# 2__ARM.net
KiCad netlist of a schematic drawn in Altium Designer
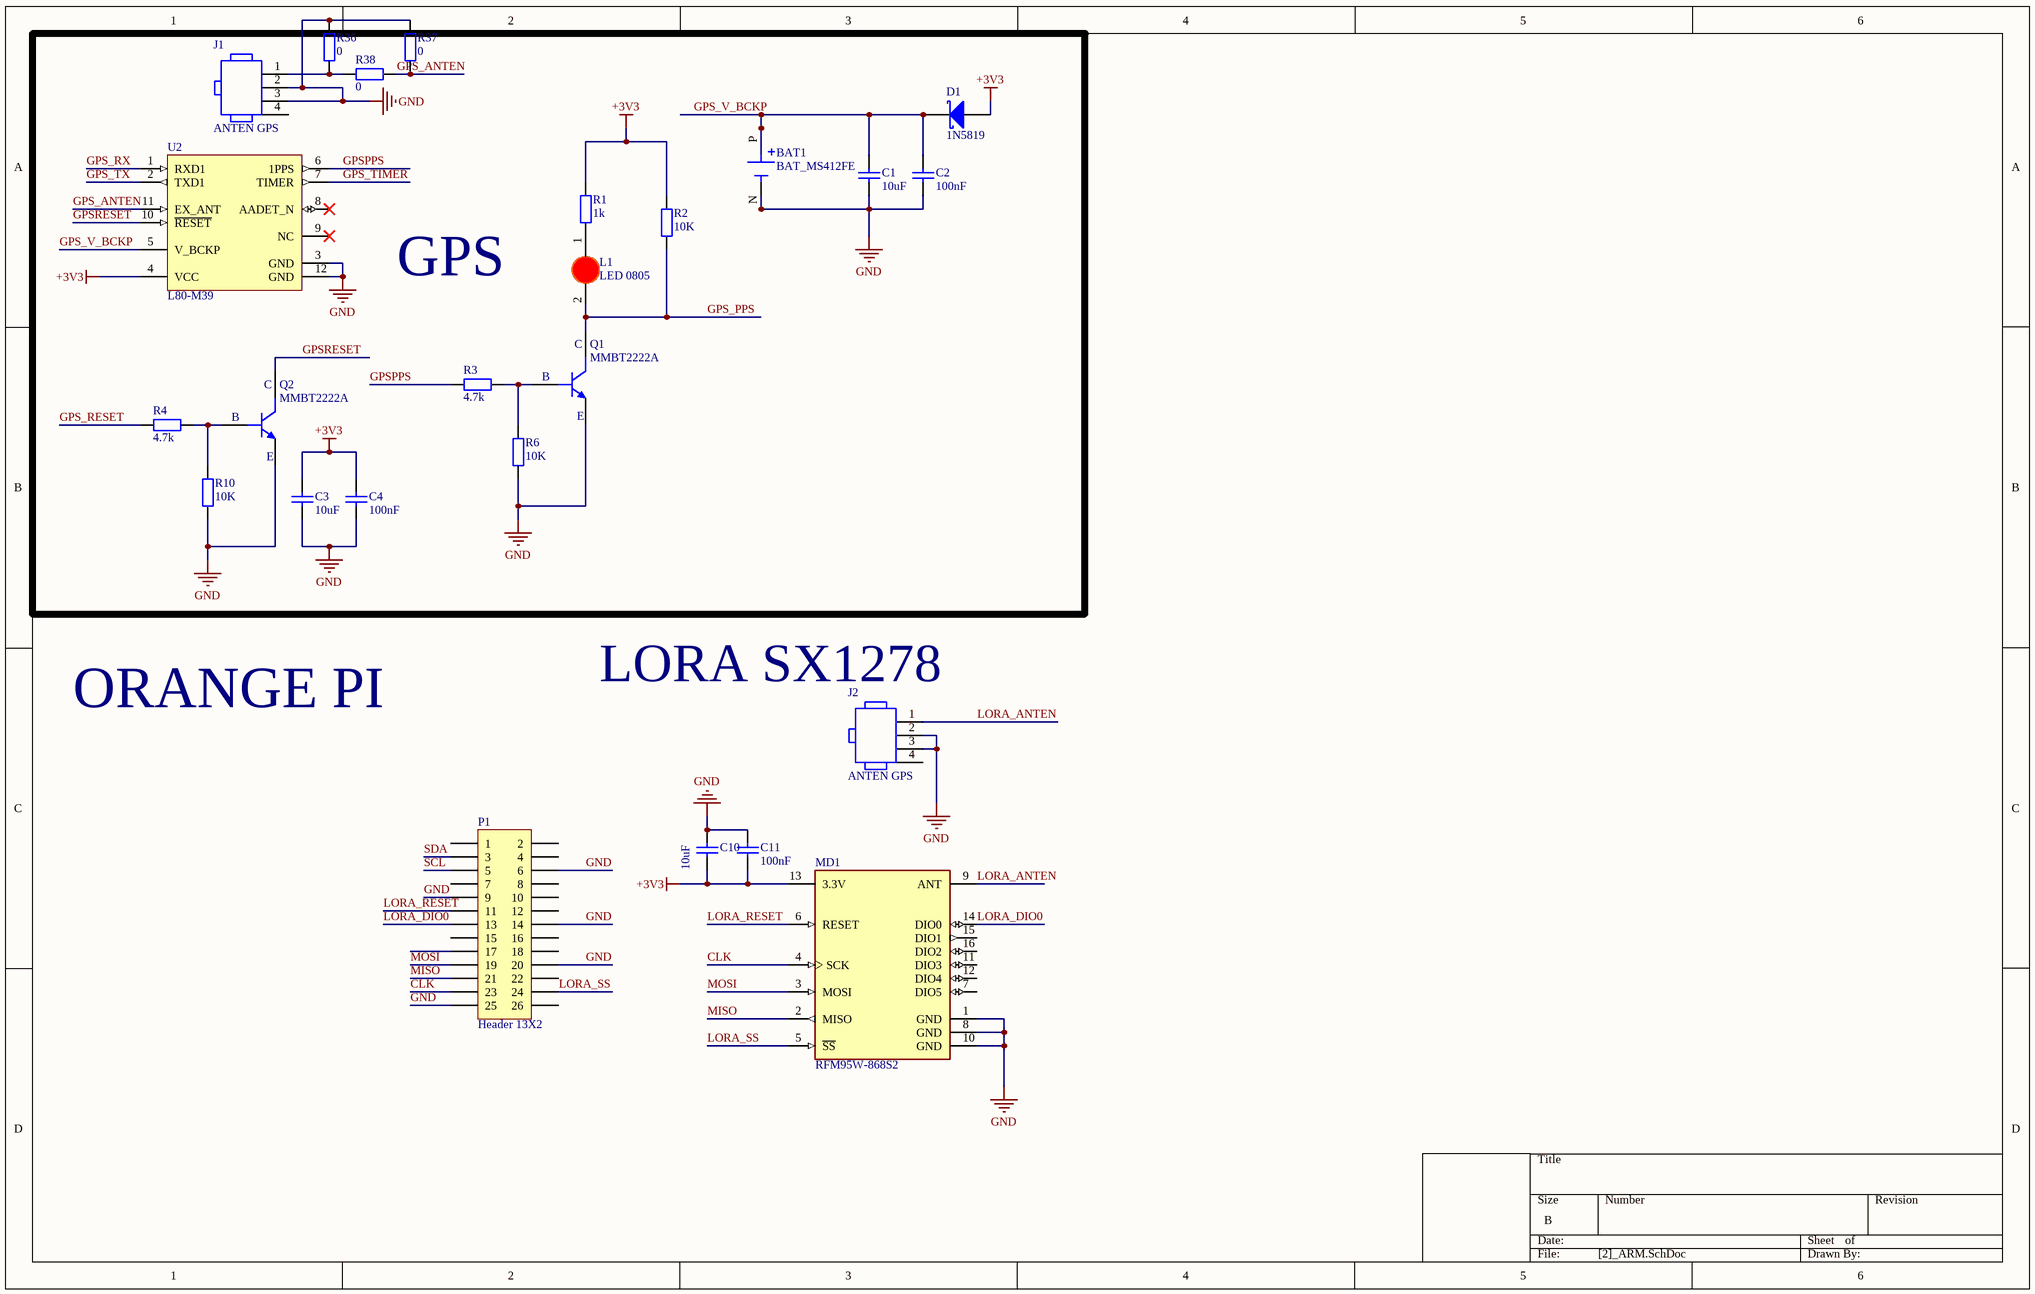
[diagram p0: [2]_ARM.SchDoc]

(export (version "E")
  (design (tool "Eeschema 10.0.6"))
  (components
    (comp (ref "BAT1")
      (value "BAT_MS412FE")
      (footprint "MS412FE")
      (libsource (lib "COMPONENT_INS") (part "BAT_MS412FE"))
    )
    (comp (ref "C1")
      (value "10uF")
      (footprint "tu 0603")
      (description "Dán")
      (libsource (lib "Altium_Lib_by_KhueNguyenCreator") (part "Tu 0603 105 16V 20%"))
    )
    (comp (ref "C2")
      (value "100nF")
      (footprint "tu 0603")
      (description "Dán")
      (libsource (lib "Altium_Lib_by_KhueNguyenCreator") (part "Tu 0603 104 50V 10%"))
    )
    (comp (ref "C3")
      (value "10uF")
      (footprint "tu 0603")
      (description "Dán")
      (libsource (lib "Altium_Lib_by_KhueNguyenCreator") (part "Tu 0603 105 16V 20%"))
    )
    (comp (ref "C4")
      (value "100nF")
      (footprint "tu 0603")
      (description "Dán")
      (libsource (lib "Altium_Lib_by_KhueNguyenCreator") (part "Tu 0603 104 50V 10%"))
    )
    (comp (ref "C10")
      (value "10uF")
      (footprint "tu 0603")
      (description "Dán")
      (libsource (lib "Altium_Lib_by_KhueNguyenCreator") (part "Tu 0603 105 16V 20%"))
    )
    (comp (ref "C11")
      (value "100nF")
      (footprint "tu 0603")
      (description "Dán")
      (libsource (lib "Altium_Lib_by_KhueNguyenCreator") (part "Tu 0603 104 50V 10%"))
    )
    (comp (ref "D1")
      (value "1N5819")
      (footprint "DO-214AA")
      (description "DIODE SCHOTTKY 1A 40V SMA DO-214AA")
      (fields (field (name "MANUFACTURER") "Fairchild") (field (name "PART NUMBER") "SS14"))
      (libsource (lib "COMPONENT_INS") (part "DIO_SS14"))
    )
    (comp (ref "J1")
      (value "ANTEN GPS")
      (footprint "TG-RECE-20369-001E-4_V")
      (description "RF Connector, Onboard Receptacle, IPEX MHFIII")
      (fields (field (name "MANUFACTURER") "Taoglas") (field (name "PARTNUMBER") "RECE-20369-001E-01"))
      (libsource (lib "Altium Content Vault") (part "TG-RECE-20369-001E-01-4"))
    )
    (comp (ref "J2")
      (value "ANTEN GPS")
      (footprint "TG-RECE-20369-001E-4_V")
      (description "RF Connector, Onboard Receptacle, IPEX MHFIII")
      (fields (field (name "MANUFACTURER") "Taoglas") (field (name "PARTNUMBER") "RECE-20369-001E-01"))
      (libsource (lib "Altium Content Vault") (part "TG-RECE-20369-001E-01-4"))
    )
    (comp (ref "L1")
      (value "LED 0805")
      (footprint "LED-0805-Red")
      (description "Dán")
      (libsource (lib "Altium_Lib_by_KhueNguyenCreator") (part "LED 0805 Do"))
    )
    (comp (ref "MD1")
      (value "RFM95W-868S2")
      (footprint "FP-RFM95W-868S2-MFG")
      (description "RX TXRX MODULE ISM < 1GHZ SMD")
      (libsource (lib "Altium Content Vault") (part "17626aa6fba47fab2b206b7c140802e"))
    )
    (comp (ref "P1")
      (value "Header 13X2")
      (footprint "HDR2X13")
      (description "Header, 13-Pin, Dual row")
      (fields (field (name "PUBLISHER") "Altium Limited"))
      (libsource (lib "Miscellaneous Connectors") (part "Header 13X2"))
    )
    (comp (ref "Q1")
      (value "MMBT2222A")
      (footprint "SOT_23_3")
      (description "MMBT2222A NPN 40V 0.6A")
      (fields (field (name "MANUFACTURER") "OEM"))
      (libsource (lib "COMPONENT_INS") (part "BJT_NPN_MMBT2222A"))
    )
    (comp (ref "Q2")
      (value "MMBT2222A")
      (footprint "SOT_23_3")
      (description "MMBT2222A NPN 40V 0.6A")
      (fields (field (name "MANUFACTURER") "OEM"))
      (libsource (lib "COMPONENT_INS") (part "BJT_NPN_MMBT2222A"))
    )
    (comp (ref "R1")
      (value "1k")
      (footprint "tro smd 0603")
      (description "Dán")
      (libsource (lib "Altium_Lib_by_KhueNguyenCreator") (part "Tro 0603 1% 4.3 k"))
    )
    (comp (ref "R2")
      (value "10K")
      (footprint "tro smd 0603")
      (description "Dán")
      (libsource (lib "Altium_Lib_by_KhueNguyenCreator") (part "Tro 0603 1% 4.3 k"))
    )
    (comp (ref "R3")
      (value "4.7k")
      (footprint "tro smd 0603")
      (description "Dán")
      (libsource (lib "Altium_Lib_by_KhueNguyenCreator") (part "Tro 0603 1% 4.3 k"))
    )
    (comp (ref "R4")
      (value "4.7k")
      (footprint "tro smd 0603")
      (description "Dán")
      (libsource (lib "Altium_Lib_by_KhueNguyenCreator") (part "Tro 0603 1% 4.3 k"))
    )
    (comp (ref "R6")
      (value "10K")
      (footprint "tro smd 0603")
      (description "Dán")
      (libsource (lib "Altium_Lib_by_KhueNguyenCreator") (part "Tro 0603 1% 4.3 k"))
    )
    (comp (ref "R10")
      (value "10K")
      (footprint "tro smd 0603")
      (description "Dán")
      (libsource (lib "Altium_Lib_by_KhueNguyenCreator") (part "Tro 0603 1% 4.3 k"))
    )
    (comp (ref "R36")
      (value "0")
      (footprint "tro smd 0603")
      (description "Dán")
      (libsource (lib "Altium_Lib_by_KhueNguyenCreator") (part "Tro 0603 1% 4.3 k"))
    )
    (comp (ref "R37")
      (value "0")
      (footprint "tro smd 0603")
      (description "Dán")
      (libsource (lib "Altium_Lib_by_KhueNguyenCreator") (part "Tro 0603 1% 4.3 k"))
    )
    (comp (ref "R38")
      (value "0")
      (footprint "tro smd 0603")
      (description "Dán")
      (libsource (lib "Altium_Lib_by_KhueNguyenCreator") (part "Tro 0603 1% 4.3 k"))
    )
    (comp (ref "U2")
      (value "L80-M39")
      (footprint "QUEC-L80-M39-12_V")
      (fields (field (name "MANUFACTURER") "Quectel"))
      (libsource (lib "Altium Content Vault") (part "QUEC-L80-M39-12"))
    )
  )
  (nets
    (net (code "1") (name "+3V3") (class "Default")
      (node (ref "C10") (pin "2") (pinfunction "2_2") (pintype "passive"))
      (node (ref "C11") (pin "2") (pinfunction "2_2") (pintype "passive"))
      (node (ref "C3") (pin "2") (pinfunction "2_2") (pintype "passive"))
      (node (ref "C4") (pin "1") (pinfunction "1_1") (pintype "passive"))
      (node (ref "D1") (pin "1") (pinfunction "A_1") (pintype "passive"))
      (node (ref "MD1") (pin "13") (pinfunction "3.3V_13") (pintype "power_in"))
      (node (ref "R1") (pin "2") (pinfunction "2_2") (pintype "passive"))
      (node (ref "R2") (pin "2") (pinfunction "2_2") (pintype "passive"))
      (node (ref "U2") (pin "4") (pinfunction "VCC_4") (pintype "power_in"))
    )
    (net (code "2") (name "/CLK") (class "Default")
      (node (ref "MD1") (pin "4") (pinfunction "SCK_4") (pintype "input"))
      (node (ref "P1") (pin "23") (pinfunction "23_23") (pintype "passive"))
    )
    (net (code "3") (name "/GPSPPS") (class "Default")
      (node (ref "R3") (pin "1") (pinfunction "1_1") (pintype "passive"))
      (node (ref "U2") (pin "6") (pinfunction "1PPS_6") (pintype "output"))
    )
    (net (code "4") (name "/GPSRESET") (class "Default")
      (node (ref "Q2") (pin "3") (pinfunction "C_3") (pintype "passive"))
      (node (ref "U2") (pin "10") (pinfunction "~{RESET}_10") (pintype "input"))
    )
    (net (code "5") (name "/GPS_ANTEN") (class "Default")
      (node (ref "R37") (pin "1") (pinfunction "1_1") (pintype "passive"))
      (node (ref "R38") (pin "1") (pinfunction "1_1") (pintype "passive"))
      (node (ref "U2") (pin "11") (pinfunction "EX_ANT_11") (pintype "input"))
    )
    (net (code "6") (name "/GPS_PPS") (class "Default")
      (node (ref "L1") (pin "2") (pinfunction "K_2") (pintype "passive"))
      (node (ref "Q1") (pin "3") (pinfunction "C_3") (pintype "passive"))
      (node (ref "R2") (pin "1") (pinfunction "1_1") (pintype "passive"))
    )
    (net (code "7") (name "/GPS_RESET") (class "Default")
      (node (ref "R4") (pin "1") (pinfunction "1_1") (pintype "passive"))
    )
    (net (code "8") (name "/GPS_RX") (class "Default")
      (node (ref "U2") (pin "1") (pinfunction "RXD1_1") (pintype "input"))
    )
    (net (code "9") (name "/GPS_TIMER") (class "Default")
      (node (ref "U2") (pin "7") (pinfunction "TIMER_7") (pintype "output"))
    )
    (net (code "10") (name "/GPS_TX") (class "Default")
      (node (ref "U2") (pin "2") (pinfunction "TXD1_2") (pintype "output"))
    )
    (net (code "11") (name "/GPS_V_BCKP") (class "Default")
      (node (ref "BAT1") (pin "P") (pinfunction "POS_P") (pintype "passive"))
      (node (ref "C1") (pin "2") (pinfunction "2_2") (pintype "passive"))
      (node (ref "C2") (pin "1") (pinfunction "1_1") (pintype "passive"))
      (node (ref "D1") (pin "2") (pinfunction "K_2") (pintype "passive"))
      (node (ref "U2") (pin "5") (pinfunction "V_BCKP_5") (pintype "power_in"))
    )
    (net (code "12") (name "/LORA_ANTEN") (class "Default")
      (node (ref "J2") (pin "1") (pinfunction "1_1") (pintype "passive"))
      (node (ref "MD1") (pin "9") (pinfunction "ANT_9") (pintype "passive"))
    )
    (net (code "13") (name "/LORA_DIO0") (class "Default")
      (node (ref "MD1") (pin "14") (pinfunction "DIO0_14") (pintype "bidirectional"))
      (node (ref "P1") (pin "13") (pinfunction "13_13") (pintype "passive"))
    )
    (net (code "14") (name "/LORA_RESET") (class "Default")
      (node (ref "MD1") (pin "6") (pinfunction "RESET_6") (pintype "input"))
      (node (ref "P1") (pin "11") (pinfunction "11_11") (pintype "passive"))
    )
    (net (code "15") (name "/LORA_SS") (class "Default")
      (node (ref "MD1") (pin "5") (pinfunction "~{SS}_5") (pintype "input"))
      (node (ref "P1") (pin "24") (pinfunction "24_24") (pintype "passive"))
    )
    (net (code "16") (name "/MISO") (class "Default")
      (node (ref "MD1") (pin "2") (pinfunction "MISO_2") (pintype "output"))
      (node (ref "P1") (pin "21") (pinfunction "21_21") (pintype "passive"))
    )
    (net (code "17") (name "/MOSI") (class "Default")
      (node (ref "MD1") (pin "3") (pinfunction "MOSI_3") (pintype "input"))
      (node (ref "P1") (pin "19") (pinfunction "19_19") (pintype "passive"))
    )
    (net (code "18") (name "/SCL") (class "Default")
      (node (ref "P1") (pin "5") (pinfunction "5_5") (pintype "passive"))
    )
    (net (code "19") (name "/SDA") (class "Default")
      (node (ref "P1") (pin "3") (pinfunction "3_3") (pintype "passive"))
    )
    (net (code "20") (name "GND") (class "Default")
      (node (ref "BAT1") (pin "N") (pinfunction "NEG_N") (pintype "passive"))
      (node (ref "C1") (pin "1") (pinfunction "1_1") (pintype "passive"))
      (node (ref "C10") (pin "1") (pinfunction "1_1") (pintype "passive"))
      (node (ref "C11") (pin "1") (pinfunction "1_1") (pintype "passive"))
      (node (ref "C2") (pin "2") (pinfunction "2_2") (pintype "passive"))
      (node (ref "C3") (pin "1") (pinfunction "1_1") (pintype "passive"))
      (node (ref "C4") (pin "2") (pinfunction "2_2") (pintype "passive"))
      (node (ref "J1") (pin "2") (pinfunction "2_2") (pintype "passive"))
      (node (ref "J1") (pin "3") (pinfunction "3_3") (pintype "passive"))
      (node (ref "J2") (pin "2") (pinfunction "2_2") (pintype "passive"))
      (node (ref "J2") (pin "3") (pinfunction "3_3") (pintype "passive"))
      (node (ref "MD1") (pin "1") (pinfunction "GND_1") (pintype "power_in"))
      (node (ref "MD1") (pin "10") (pinfunction "GND_10") (pintype "power_in"))
      (node (ref "MD1") (pin "8") (pinfunction "GND_8") (pintype "power_in"))
      (node (ref "P1") (pin "14") (pinfunction "14_14") (pintype "passive"))
      (node (ref "P1") (pin "20") (pinfunction "20_20") (pintype "passive"))
      (node (ref "P1") (pin "25") (pinfunction "25_25") (pintype "passive"))
      (node (ref "P1") (pin "6") (pinfunction "6_6") (pintype "passive"))
      (node (ref "P1") (pin "9") (pinfunction "9_9") (pintype "passive"))
      (node (ref "Q1") (pin "2") (pinfunction "E_2") (pintype "passive"))
      (node (ref "Q2") (pin "2") (pinfunction "E_2") (pintype "passive"))
      (node (ref "R10") (pin "1") (pinfunction "1_1") (pintype "passive"))
      (node (ref "R36") (pin "2") (pinfunction "2_2") (pintype "passive"))
      (node (ref "R37") (pin "2") (pinfunction "2_2") (pintype "passive"))
      (node (ref "R6") (pin "1") (pinfunction "1_1") (pintype "passive"))
      (node (ref "U2") (pin "12") (pinfunction "GND_12") (pintype "power_in"))
      (node (ref "U2") (pin "3") (pinfunction "GND_3") (pintype "power_in"))
    )
    (net (code "21") (name "Net-(J1-Pad1)") (class "Default")
      (node (ref "J1") (pin "1") (pinfunction "1_1") (pintype "passive"))
      (node (ref "R36") (pin "1") (pinfunction "1_1") (pintype "passive"))
      (node (ref "R38") (pin "2") (pinfunction "2_2") (pintype "passive"))
    )
    (net (code "22") (name "Net-(L1-A)") (class "Default")
      (node (ref "L1") (pin "1") (pinfunction "A_1") (pintype "passive"))
      (node (ref "R1") (pin "1") (pinfunction "1_1") (pintype "passive"))
    )
    (net (code "23") (name "Net-(Q1-B)") (class "Default")
      (node (ref "Q1") (pin "1") (pinfunction "B_1") (pintype "passive"))
      (node (ref "R3") (pin "2") (pinfunction "2_2") (pintype "passive"))
      (node (ref "R6") (pin "2") (pinfunction "2_2") (pintype "passive"))
    )
    (net (code "24") (name "Net-(Q2-B)") (class "Default")
      (node (ref "Q2") (pin "1") (pinfunction "B_1") (pintype "passive"))
      (node (ref "R10") (pin "2") (pinfunction "2_2") (pintype "passive"))
      (node (ref "R4") (pin "2") (pinfunction "2_2") (pintype "passive"))
    )
    (net (code "25") (name "unconnected-(J1-Pad4)") (class "Default")
      (node (ref "J1") (pin "4") (pinfunction "4_4") (pintype "passive"))
    )
    (net (code "26") (name "unconnected-(J2-Pad4)") (class "Default")
      (node (ref "J2") (pin "4") (pinfunction "4_4") (pintype "passive"))
    )
    (net (code "27") (name "unconnected-(MD1-DIO1-Pad15)") (class "Default")
      (node (ref "MD1") (pin "15") (pinfunction "DIO1_15") (pintype "output"))
    )
    (net (code "28") (name "unconnected-(MD1-DIO2-Pad16)") (class "Default")
      (node (ref "MD1") (pin "16") (pinfunction "DIO2_16") (pintype "bidirectional"))
    )
    (net (code "29") (name "unconnected-(MD1-DIO3-Pad11)") (class "Default")
      (node (ref "MD1") (pin "11") (pinfunction "DIO3_11") (pintype "bidirectional"))
    )
    (net (code "30") (name "unconnected-(MD1-DIO4-Pad12)") (class "Default")
      (node (ref "MD1") (pin "12") (pinfunction "DIO4_12") (pintype "bidirectional"))
    )
    (net (code "31") (name "unconnected-(MD1-DIO5-Pad7)") (class "Default")
      (node (ref "MD1") (pin "7") (pinfunction "DIO5_7") (pintype "bidirectional"))
    )
    (net (code "32") (name "unconnected-(P1-Pad1)") (class "Default")
      (node (ref "P1") (pin "1") (pinfunction "1_1") (pintype "passive"))
    )
    (net (code "33") (name "unconnected-(P1-Pad2)") (class "Default")
      (node (ref "P1") (pin "2") (pinfunction "2_2") (pintype "passive"))
    )
    (net (code "34") (name "unconnected-(P1-Pad4)") (class "Default")
      (node (ref "P1") (pin "4") (pinfunction "4_4") (pintype "passive"))
    )
    (net (code "35") (name "unconnected-(P1-Pad7)") (class "Default")
      (node (ref "P1") (pin "7") (pinfunction "7_7") (pintype "passive"))
    )
    (net (code "36") (name "unconnected-(P1-Pad8)") (class "Default")
      (node (ref "P1") (pin "8") (pinfunction "8_8") (pintype "passive"))
    )
    (net (code "37") (name "unconnected-(P1-Pad10)") (class "Default")
      (node (ref "P1") (pin "10") (pinfunction "10_10") (pintype "passive"))
    )
    (net (code "38") (name "unconnected-(P1-Pad12)") (class "Default")
      (node (ref "P1") (pin "12") (pinfunction "12_12") (pintype "passive"))
    )
    (net (code "39") (name "unconnected-(P1-Pad15)") (class "Default")
      (node (ref "P1") (pin "15") (pinfunction "15_15") (pintype "passive"))
    )
    (net (code "40") (name "unconnected-(P1-Pad16)") (class "Default")
      (node (ref "P1") (pin "16") (pinfunction "16_16") (pintype "passive"))
    )
    (net (code "41") (name "unconnected-(P1-Pad17)") (class "Default")
      (node (ref "P1") (pin "17") (pinfunction "17_17") (pintype "passive"))
    )
    (net (code "42") (name "unconnected-(P1-Pad18)") (class "Default")
      (node (ref "P1") (pin "18") (pinfunction "18_18") (pintype "passive"))
    )
    (net (code "43") (name "unconnected-(P1-Pad22)") (class "Default")
      (node (ref "P1") (pin "22") (pinfunction "22_22") (pintype "passive"))
    )
    (net (code "44") (name "unconnected-(P1-Pad26)") (class "Default")
      (node (ref "P1") (pin "26") (pinfunction "26_26") (pintype "passive"))
    )
    (net (code "45") (name "unconnected-(U2-AADET_N-Pad8)") (class "Default")
      (node (ref "U2") (pin "8") (pinfunction "AADET_N_8") (pintype "bidirectional+no_connect"))
    )
    (net (code "46") (name "unconnected-(U2-NC-Pad9)") (class "Default")
      (node (ref "U2") (pin "9") (pinfunction "NC_9") (pintype "passive+no_connect"))
    )
  )
)
